# RPM.net
KiCad netlist of a schematic drawn in EAGLE
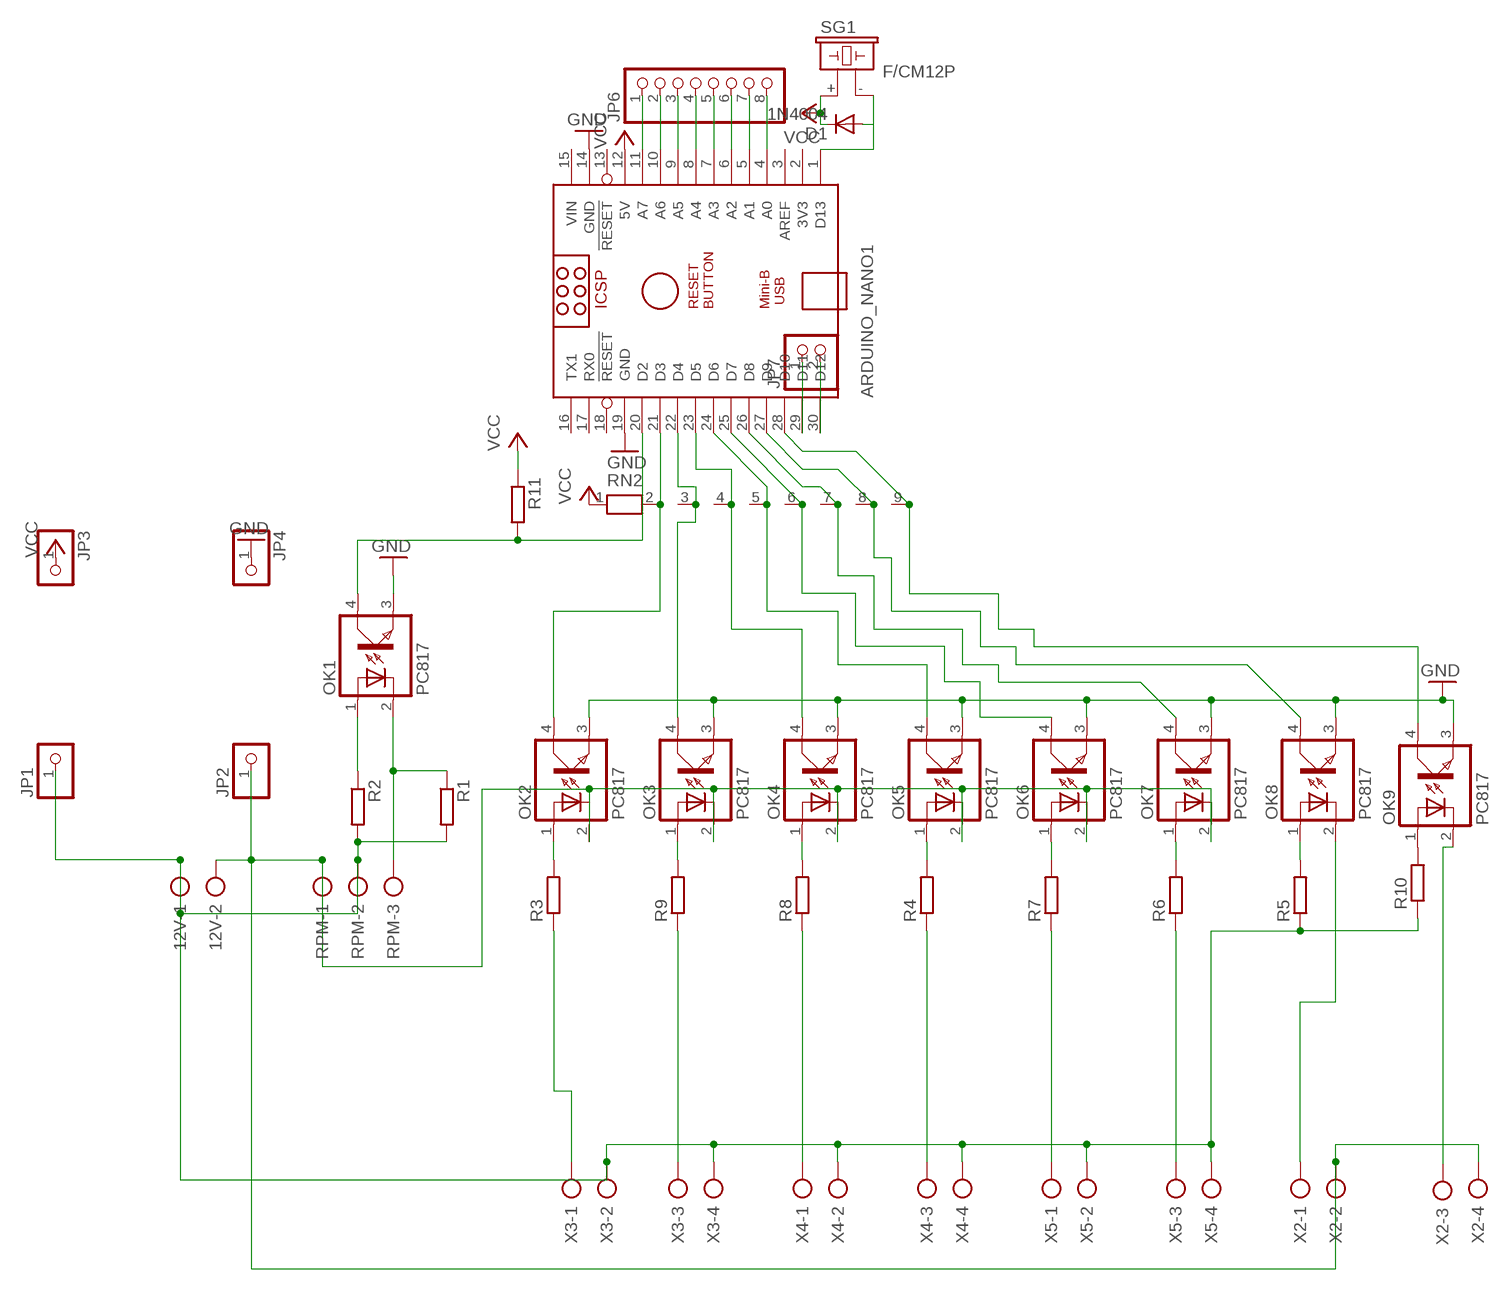
[diagram p0: schematic, sheet 1]

(export (version "E")
  (design (tool "Eeschema 10.0.6"))
  (components
    (comp (ref "12V")
      (value "AK300/2")
      (footprint "eagle-import:AK300_2")
      (libsource (lib "eagle-import") (part "AK300/2"))
    )
    (comp (ref "ARDUINO_NANO1")
      (value "ARDUINO_NANO")
      (footprint "eagle-import:ARDUINO_NANO")
      (libsource (lib "eagle-import") (part "ARDUINO_NANO"))
    )
    (comp (ref "D1")
      (value "1N4004")
      (footprint "eagle-import:DO41-10")
      (libsource (lib "eagle-import") (part "1N4004"))
    )
    (comp (ref "JP1")
      (value "PINHD-1X1")
      (footprint "eagle-import:1X01")
      (libsource (lib "eagle-import") (part "PINHD-1X1"))
    )
    (comp (ref "JP2")
      (value "PINHD-1X1")
      (footprint "eagle-import:1X01")
      (libsource (lib "eagle-import") (part "PINHD-1X1"))
    )
    (comp (ref "JP3")
      (value "PINHD-1X1")
      (footprint "eagle-import:1X01")
      (libsource (lib "eagle-import") (part "PINHD-1X1"))
    )
    (comp (ref "JP4")
      (value "PINHD-1X1")
      (footprint "eagle-import:1X01")
      (libsource (lib "eagle-import") (part "PINHD-1X1"))
    )
    (comp (ref "JP6")
      (value "PINHD-1X8")
      (footprint "eagle-import:1X08")
      (libsource (lib "eagle-import") (part "PINHD-1X8"))
    )
    (comp (ref "JP7")
      (value "PINHD-1X2")
      (footprint "eagle-import:1X02")
      (libsource (lib "eagle-import") (part "PINHD-1X2"))
    )
    (comp (ref "OK1")
      (value "PC817")
      (footprint "eagle-import:DIL04")
      (fields (field (name "MPN") "PC817X4J000F"))
      (libsource (lib "eagle-import") (part "PC817"))
    )
    (comp (ref "OK2")
      (value "PC817")
      (footprint "eagle-import:DIL04")
      (fields (field (name "MPN") "PC817X4J000F"))
      (libsource (lib "eagle-import") (part "PC817"))
    )
    (comp (ref "OK3")
      (value "PC817")
      (footprint "eagle-import:DIL04")
      (fields (field (name "MPN") "PC817X4J000F"))
      (libsource (lib "eagle-import") (part "PC817"))
    )
    (comp (ref "OK4")
      (value "PC817")
      (footprint "eagle-import:DIL04")
      (fields (field (name "MPN") "PC817X4J000F"))
      (libsource (lib "eagle-import") (part "PC817"))
    )
    (comp (ref "OK5")
      (value "PC817")
      (footprint "eagle-import:DIL04")
      (fields (field (name "MPN") "PC817X4J000F"))
      (libsource (lib "eagle-import") (part "PC817"))
    )
    (comp (ref "OK6")
      (value "PC817")
      (footprint "eagle-import:DIL04")
      (fields (field (name "MPN") "PC817X4J000F"))
      (libsource (lib "eagle-import") (part "PC817"))
    )
    (comp (ref "OK7")
      (value "PC817")
      (footprint "eagle-import:DIL04")
      (fields (field (name "MPN") "PC817X4J000F"))
      (libsource (lib "eagle-import") (part "PC817"))
    )
    (comp (ref "OK8")
      (value "PC817")
      (footprint "eagle-import:DIL04")
      (fields (field (name "MPN") "PC817X4J000F"))
      (libsource (lib "eagle-import") (part "PC817"))
    )
    (comp (ref "OK9")
      (value "PC817")
      (footprint "eagle-import:DIL04")
      (fields (field (name "MPN") "PC817X4J000F"))
      (libsource (lib "eagle-import") (part "PC817"))
    )
    (comp (ref "R1")
      (value "R-EU_0204/7")
      (footprint "eagle-import:0204_7")
      (libsource (lib "eagle-import") (part "R-EU_0204/7"))
    )
    (comp (ref "R2")
      (value "R-EU_0204/7")
      (footprint "eagle-import:0204_7")
      (libsource (lib "eagle-import") (part "resistor_R-EU_0204/7"))
    )
    (comp (ref "R3")
      (value "R-EU_0204/7")
      (footprint "eagle-import:0204_7")
      (libsource (lib "eagle-import") (part "resistor_R-EU_0204/7"))
    )
    (comp (ref "R4")
      (value "R-EU_0204/7")
      (footprint "eagle-import:0204_7")
      (libsource (lib "eagle-import") (part "resistor_R-EU_0204/7"))
    )
    (comp (ref "R5")
      (value "R-EU_0204/7")
      (footprint "eagle-import:0204_7")
      (libsource (lib "eagle-import") (part "R-EU_0204/7"))
    )
    (comp (ref "R6")
      (value "R-EU_0204/7")
      (footprint "eagle-import:0204_7")
      (libsource (lib "eagle-import") (part "resistor_R-EU_0204/7"))
    )
    (comp (ref "R7")
      (value "R-EU_0204/7")
      (footprint "eagle-import:0204_7")
      (libsource (lib "eagle-import") (part "resistor_R-EU_0204/7"))
    )
    (comp (ref "R8")
      (value "R-EU_0204/7")
      (footprint "eagle-import:0204_7")
      (libsource (lib "eagle-import") (part "resistor_R-EU_0204/7"))
    )
    (comp (ref "R9")
      (value "R-EU_0204/7")
      (footprint "eagle-import:0204_7")
      (libsource (lib "eagle-import") (part "resistor_R-EU_0204/7"))
    )
    (comp (ref "R10")
      (value "R-EU_0204/7")
      (footprint "eagle-import:0204_7")
      (libsource (lib "eagle-import") (part "R-EU_0204/7"))
    )
    (comp (ref "R11")
      (value "R-EU_0204/7")
      (footprint "eagle-import:0204_7")
      (libsource (lib "eagle-import") (part "R-EU_0204/7"))
    )
    (comp (ref "RN2")
      (value "RN08")
      (footprint "eagle-import:RN-9")
      (libsource (lib "eagle-import") (part "RN08"))
    )
    (comp (ref "RPM")
      (value "AK300/3")
      (footprint "eagle-import:AK300_3")
      (libsource (lib "eagle-import") (part "AK300/3"))
    )
    (comp (ref "SG1")
      (value "F/CM12P")
      (footprint "eagle-import:F_CM12P")
      (libsource (lib "eagle-import") (part "F/CM12P"))
    )
    (comp (ref "X2")
      (value "AK300/4")
      (footprint "eagle-import:AK300_4")
      (libsource (lib "eagle-import") (part "AK300/4"))
    )
    (comp (ref "X3")
      (value "AK300/4")
      (footprint "eagle-import:AK300_4")
      (libsource (lib "eagle-import") (part "AK300/4"))
    )
    (comp (ref "X4")
      (value "AK300/4")
      (footprint "eagle-import:AK300_4")
      (libsource (lib "eagle-import") (part "AK300/4"))
    )
    (comp (ref "X5")
      (value "AK300/4")
      (footprint "eagle-import:AK300_4")
      (libsource (lib "eagle-import") (part "AK300/4"))
    )
  )
  (nets
    (net (code "1") (name "/VIN") (class "Default")
      (node (ref "ARDUINO_NANO1") (pin "15") (pinfunction "VIN_15") (pintype "power_in"))
    )
    (net (code "2") (name "GND") (class "Default")
      (node (ref "ARDUINO_NANO1") (pin "14") (pinfunction "GND_14") (pintype "power_in"))
      (node (ref "ARDUINO_NANO1") (pin "19") (pinfunction "GND_19") (pintype "power_in"))
      (node (ref "JP4") (pin "1") (pinfunction "1_1") (pintype "passive"))
      (node (ref "OK1") (pin "3") (pinfunction "EMIT_3") (pintype "passive"))
      (node (ref "OK2") (pin "3") (pinfunction "EMIT_3") (pintype "passive"))
      (node (ref "OK3") (pin "3") (pinfunction "EMIT_3") (pintype "passive"))
      (node (ref "OK4") (pin "3") (pinfunction "EMIT_3") (pintype "passive"))
      (node (ref "OK5") (pin "3") (pinfunction "EMIT_3") (pintype "passive"))
      (node (ref "OK6") (pin "3") (pinfunction "EMIT_3") (pintype "passive"))
      (node (ref "OK7") (pin "3") (pinfunction "EMIT_3") (pintype "passive"))
      (node (ref "OK8") (pin "3") (pinfunction "EMIT_3") (pintype "passive"))
      (node (ref "OK9") (pin "3") (pinfunction "EMIT_3") (pintype "passive"))
    )
    (net (code "3") (name "Net-(12VA-KL)") (class "Default")
      (node (ref "12V") (pin "1") (pinfunction "KL_1") (pintype "passive"))
      (node (ref "JP1") (pin "1") (pinfunction "1_1") (pintype "passive"))
      (node (ref "R1") (pin "2") (pinfunction "2_2") (pintype "passive"))
      (node (ref "R10") (pin "1") (pinfunction "1_1") (pintype "passive"))
      (node (ref "R2") (pin "2") (pinfunction "2_2") (pintype "passive"))
      (node (ref "R5") (pin "1") (pinfunction "1_1") (pintype "passive"))
      (node (ref "RPM") (pin "2") (pinfunction "KL_2") (pintype "passive"))
      (node (ref "X3") (pin "2") (pinfunction "KL_2") (pintype "passive"))
      (node (ref "X3") (pin "4") (pinfunction "KL_4") (pintype "passive"))
      (node (ref "X4") (pin "2") (pinfunction "KL_2") (pintype "passive"))
      (node (ref "X4") (pin "4") (pinfunction "KL_4") (pintype "passive"))
      (node (ref "X5") (pin "2") (pinfunction "KL_2") (pintype "passive"))
      (node (ref "X5") (pin "4") (pinfunction "KL_4") (pintype "passive"))
    )
    (net (code "4") (name "Net-(12VB-KL)") (class "Default")
      (node (ref "12V") (pin "2") (pinfunction "KL_2") (pintype "passive"))
      (node (ref "JP2") (pin "1") (pinfunction "1_1") (pintype "passive"))
      (node (ref "OK2") (pin "2") (pinfunction "C_2") (pintype "passive"))
      (node (ref "OK3") (pin "2") (pinfunction "C_2") (pintype "passive"))
      (node (ref "OK4") (pin "2") (pinfunction "C_2") (pintype "passive"))
      (node (ref "OK5") (pin "2") (pinfunction "C_2") (pintype "passive"))
      (node (ref "OK6") (pin "2") (pinfunction "C_2") (pintype "passive"))
      (node (ref "OK7") (pin "2") (pinfunction "C_2") (pintype "passive"))
      (node (ref "RPM") (pin "1") (pinfunction "KL_1") (pintype "passive"))
      (node (ref "X2") (pin "2") (pinfunction "KL_2") (pintype "passive"))
      (node (ref "X2") (pin "4") (pinfunction "KL_4") (pintype "passive"))
    )
    (net (code "5") (name "Net-(ARDUINO_NANO1-A0)") (class "Default")
      (node (ref "ARDUINO_NANO1") (pin "4") (pinfunction "A0_4") (pintype "bidirectional"))
      (node (ref "JP6") (pin "8") (pinfunction "8_8") (pintype "passive"))
    )
    (net (code "6") (name "Net-(ARDUINO_NANO1-A1)") (class "Default")
      (node (ref "ARDUINO_NANO1") (pin "5") (pinfunction "A1_5") (pintype "bidirectional"))
      (node (ref "JP6") (pin "7") (pinfunction "7_7") (pintype "passive"))
    )
    (net (code "7") (name "Net-(ARDUINO_NANO1-A2)") (class "Default")
      (node (ref "ARDUINO_NANO1") (pin "6") (pinfunction "A2_6") (pintype "bidirectional"))
      (node (ref "JP6") (pin "6") (pinfunction "6_6") (pintype "passive"))
    )
    (net (code "8") (name "Net-(ARDUINO_NANO1-A3)") (class "Default")
      (node (ref "ARDUINO_NANO1") (pin "7") (pinfunction "A3_7") (pintype "bidirectional"))
      (node (ref "JP6") (pin "5") (pinfunction "5_5") (pintype "passive"))
    )
    (net (code "9") (name "Net-(ARDUINO_NANO1-A4)") (class "Default")
      (node (ref "ARDUINO_NANO1") (pin "8") (pinfunction "A4_8") (pintype "bidirectional"))
      (node (ref "JP6") (pin "4") (pinfunction "4_4") (pintype "passive"))
    )
    (net (code "10") (name "Net-(ARDUINO_NANO1-A5)") (class "Default")
      (node (ref "ARDUINO_NANO1") (pin "9") (pinfunction "A5_9") (pintype "bidirectional"))
      (node (ref "JP6") (pin "3") (pinfunction "3_3") (pintype "passive"))
    )
    (net (code "11") (name "Net-(ARDUINO_NANO1-A6)") (class "Default")
      (node (ref "ARDUINO_NANO1") (pin "10") (pinfunction "A6_10") (pintype "bidirectional"))
      (node (ref "JP6") (pin "2") (pinfunction "2_2") (pintype "passive"))
    )
    (net (code "12") (name "Net-(ARDUINO_NANO1-A7)") (class "Default")
      (node (ref "ARDUINO_NANO1") (pin "11") (pinfunction "A7_11") (pintype "bidirectional"))
      (node (ref "JP6") (pin "1") (pinfunction "1_1") (pintype "passive"))
    )
    (net (code "13") (name "Net-(ARDUINO_NANO1-D2)") (class "Default")
      (node (ref "ARDUINO_NANO1") (pin "20") (pinfunction "D2_20") (pintype "bidirectional"))
      (node (ref "OK1") (pin "4") (pinfunction "COL_4") (pintype "passive"))
      (node (ref "R11") (pin "2") (pinfunction "2_2") (pintype "passive"))
    )
    (net (code "14") (name "Net-(ARDUINO_NANO1-D3)") (class "Default")
      (node (ref "ARDUINO_NANO1") (pin "21") (pinfunction "D3_21") (pintype "bidirectional"))
      (node (ref "OK2") (pin "4") (pinfunction "COL_4") (pintype "passive"))
      (node (ref "RN2") (pin "2") (pinfunction "2_2") (pintype "passive"))
    )
    (net (code "15") (name "Net-(ARDUINO_NANO1-D4)") (class "Default")
      (node (ref "ARDUINO_NANO1") (pin "22") (pinfunction "D4_22") (pintype "bidirectional"))
      (node (ref "OK3") (pin "4") (pinfunction "COL_4") (pintype "passive"))
      (node (ref "RN2") (pin "3") (pinfunction "3_3") (pintype "passive"))
    )
    (net (code "16") (name "Net-(ARDUINO_NANO1-D5)") (class "Default")
      (node (ref "ARDUINO_NANO1") (pin "23") (pinfunction "D5_23") (pintype "bidirectional"))
      (node (ref "OK4") (pin "4") (pinfunction "COL_4") (pintype "passive"))
      (node (ref "RN2") (pin "4") (pinfunction "4_4") (pintype "passive"))
    )
    (net (code "17") (name "Net-(ARDUINO_NANO1-D6)") (class "Default")
      (node (ref "ARDUINO_NANO1") (pin "24") (pinfunction "D6_24") (pintype "bidirectional"))
      (node (ref "OK5") (pin "4") (pinfunction "COL_4") (pintype "passive"))
      (node (ref "RN2") (pin "5") (pinfunction "5_5") (pintype "passive"))
    )
    (net (code "18") (name "Net-(ARDUINO_NANO1-D7)") (class "Default")
      (node (ref "ARDUINO_NANO1") (pin "25") (pinfunction "D7_25") (pintype "bidirectional"))
      (node (ref "OK6") (pin "4") (pinfunction "COL_4") (pintype "passive"))
      (node (ref "RN2") (pin "6") (pinfunction "6_6") (pintype "passive"))
    )
    (net (code "19") (name "Net-(ARDUINO_NANO1-D8)") (class "Default")
      (node (ref "ARDUINO_NANO1") (pin "26") (pinfunction "D8_26") (pintype "bidirectional"))
      (node (ref "OK7") (pin "4") (pinfunction "COL_4") (pintype "passive"))
      (node (ref "RN2") (pin "7") (pinfunction "7_7") (pintype "passive"))
    )
    (net (code "20") (name "Net-(ARDUINO_NANO1-D9)") (class "Default")
      (node (ref "ARDUINO_NANO1") (pin "27") (pinfunction "D9_27") (pintype "bidirectional"))
      (node (ref "OK8") (pin "4") (pinfunction "COL_4") (pintype "passive"))
      (node (ref "RN2") (pin "8") (pinfunction "8_8") (pintype "passive"))
    )
    (net (code "21") (name "Net-(ARDUINO_NANO1-D10)") (class "Default")
      (node (ref "ARDUINO_NANO1") (pin "28") (pinfunction "D10_28") (pintype "bidirectional"))
      (node (ref "OK9") (pin "4") (pinfunction "COL_4") (pintype "passive"))
      (node (ref "RN2") (pin "9") (pinfunction "9_9") (pintype "passive"))
    )
    (net (code "22") (name "Net-(ARDUINO_NANO1-D11)") (class "Default")
      (node (ref "ARDUINO_NANO1") (pin "29") (pinfunction "D11_29") (pintype "bidirectional"))
      (node (ref "JP7") (pin "1") (pinfunction "1_1") (pintype "passive"))
    )
    (net (code "23") (name "Net-(ARDUINO_NANO1-D12)") (class "Default")
      (node (ref "ARDUINO_NANO1") (pin "30") (pinfunction "D12_30") (pintype "bidirectional"))
      (node (ref "JP7") (pin "2") (pinfunction "2_2") (pintype "passive"))
    )
    (net (code "24") (name "Net-(ARDUINO_NANO1-D13)") (class "Default")
      (node (ref "ARDUINO_NANO1") (pin "1") (pinfunction "D13_1") (pintype "bidirectional"))
      (node (ref "D1") (pin "A") (pinfunction "A_A") (pintype "passive"))
      (node (ref "SG1") (pin "-") (pinfunction "2_-") (pintype "passive"))
    )
    (net (code "25") (name "Net-(OK1-A)") (class "Default")
      (node (ref "OK1") (pin "1") (pinfunction "A_1") (pintype "passive"))
      (node (ref "R2") (pin "1") (pinfunction "1_1") (pintype "passive"))
    )
    (net (code "26") (name "Net-(OK1-C)") (class "Default")
      (node (ref "OK1") (pin "2") (pinfunction "C_2") (pintype "passive"))
      (node (ref "R1") (pin "1") (pinfunction "1_1") (pintype "passive"))
      (node (ref "RPM") (pin "3") (pinfunction "KL_3") (pintype "passive"))
    )
    (net (code "27") (name "Net-(OK2-A)") (class "Default")
      (node (ref "OK2") (pin "1") (pinfunction "A_1") (pintype "passive"))
      (node (ref "R3") (pin "2") (pinfunction "2_2") (pintype "passive"))
    )
    (net (code "28") (name "Net-(OK3-A)") (class "Default")
      (node (ref "OK3") (pin "1") (pinfunction "A_1") (pintype "passive"))
      (node (ref "R9") (pin "2") (pinfunction "2_2") (pintype "passive"))
    )
    (net (code "29") (name "Net-(OK4-A)") (class "Default")
      (node (ref "OK4") (pin "1") (pinfunction "A_1") (pintype "passive"))
      (node (ref "R8") (pin "2") (pinfunction "2_2") (pintype "passive"))
    )
    (net (code "30") (name "Net-(OK5-A)") (class "Default")
      (node (ref "OK5") (pin "1") (pinfunction "A_1") (pintype "passive"))
      (node (ref "R4") (pin "2") (pinfunction "2_2") (pintype "passive"))
    )
    (net (code "31") (name "Net-(OK6-A)") (class "Default")
      (node (ref "OK6") (pin "1") (pinfunction "A_1") (pintype "passive"))
      (node (ref "R7") (pin "2") (pinfunction "2_2") (pintype "passive"))
    )
    (net (code "32") (name "Net-(OK7-A)") (class "Default")
      (node (ref "OK7") (pin "1") (pinfunction "A_1") (pintype "passive"))
      (node (ref "R6") (pin "2") (pinfunction "2_2") (pintype "passive"))
    )
    (net (code "33") (name "Net-(OK8-A)") (class "Default")
      (node (ref "OK8") (pin "1") (pinfunction "A_1") (pintype "passive"))
      (node (ref "R5") (pin "2") (pinfunction "2_2") (pintype "passive"))
    )
    (net (code "34") (name "Net-(OK8-C)") (class "Default")
      (node (ref "OK8") (pin "2") (pinfunction "C_2") (pintype "passive"))
      (node (ref "X2") (pin "1") (pinfunction "KL_1") (pintype "passive"))
    )
    (net (code "35") (name "Net-(OK9-A)") (class "Default")
      (node (ref "OK9") (pin "1") (pinfunction "A_1") (pintype "passive"))
      (node (ref "R10") (pin "2") (pinfunction "2_2") (pintype "passive"))
    )
    (net (code "36") (name "Net-(OK9-C)") (class "Default")
      (node (ref "OK9") (pin "2") (pinfunction "C_2") (pintype "passive"))
      (node (ref "X2") (pin "3") (pinfunction "KL_3") (pintype "passive"))
    )
    (net (code "37") (name "Net-(X3A-KL)") (class "Default")
      (node (ref "R3") (pin "1") (pinfunction "1_1") (pintype "passive"))
      (node (ref "X3") (pin "1") (pinfunction "KL_1") (pintype "passive"))
    )
    (net (code "38") (name "Net-(X3C-KL)") (class "Default")
      (node (ref "R9") (pin "1") (pinfunction "1_1") (pintype "passive"))
      (node (ref "X3") (pin "3") (pinfunction "KL_3") (pintype "passive"))
    )
    (net (code "39") (name "Net-(X4A-KL)") (class "Default")
      (node (ref "R8") (pin "1") (pinfunction "1_1") (pintype "passive"))
      (node (ref "X4") (pin "1") (pinfunction "KL_1") (pintype "passive"))
    )
    (net (code "40") (name "Net-(X4C-KL)") (class "Default")
      (node (ref "R4") (pin "1") (pinfunction "1_1") (pintype "passive"))
      (node (ref "X4") (pin "3") (pinfunction "KL_3") (pintype "passive"))
    )
    (net (code "41") (name "Net-(X5A-KL)") (class "Default")
      (node (ref "R7") (pin "1") (pinfunction "1_1") (pintype "passive"))
      (node (ref "X5") (pin "1") (pinfunction "KL_1") (pintype "passive"))
    )
    (net (code "42") (name "Net-(X5C-KL)") (class "Default")
      (node (ref "R6") (pin "1") (pinfunction "1_1") (pintype "passive"))
      (node (ref "X5") (pin "3") (pinfunction "KL_3") (pintype "passive"))
    )
    (net (code "43") (name "VCC") (class "Default")
      (node (ref "ARDUINO_NANO1") (pin "12") (pinfunction "5V_12") (pintype "power_in"))
      (node (ref "D1") (pin "C") (pinfunction "C_C") (pintype "passive"))
      (node (ref "JP3") (pin "1") (pinfunction "1_1") (pintype "passive"))
      (node (ref "R11") (pin "1") (pinfunction "1_1") (pintype "passive"))
      (node (ref "RN2") (pin "1") (pinfunction "1_1") (pintype "passive"))
      (node (ref "SG1") (pin "+") (pinfunction "1_+") (pintype "passive"))
    )
    (net (code "44") (name "unconnected-(ARDUINO_NANO1-3V3-Pad2)") (class "Default")
      (node (ref "ARDUINO_NANO1") (pin "2") (pinfunction "3V3_2") (pintype "output"))
    )
    (net (code "45") (name "unconnected-(ARDUINO_NANO1-AREF-Pad3)") (class "Default")
      (node (ref "ARDUINO_NANO1") (pin "3") (pinfunction "AREF_3") (pintype "input"))
    )
    (net (code "46") (name "unconnected-(ARDUINO_NANO1-RX0-Pad17)") (class "Default")
      (node (ref "ARDUINO_NANO1") (pin "17") (pinfunction "RX0_17") (pintype "bidirectional"))
    )
    (net (code "47") (name "unconnected-(ARDUINO_NANO1-TX1-Pad16)") (class "Default")
      (node (ref "ARDUINO_NANO1") (pin "16") (pinfunction "TX1_16") (pintype "bidirectional"))
    )
    (net (code "48") (name "unconnected-(ARDUINO_NANO1-~{RESET}-Pad13)") (class "Default")
      (node (ref "ARDUINO_NANO1") (pin "13") (pinfunction "~{RESET}_13") (pintype "input"))
    )
    (net (code "49") (name "unconnected-(ARDUINO_NANO1-~{RESET}-Pad18)") (class "Default")
      (node (ref "ARDUINO_NANO1") (pin "18") (pinfunction "~{RESET}_18") (pintype "input"))
    )
  )
)
